# portal.net
KiCad netlist of a schematic drawn in EAGLE
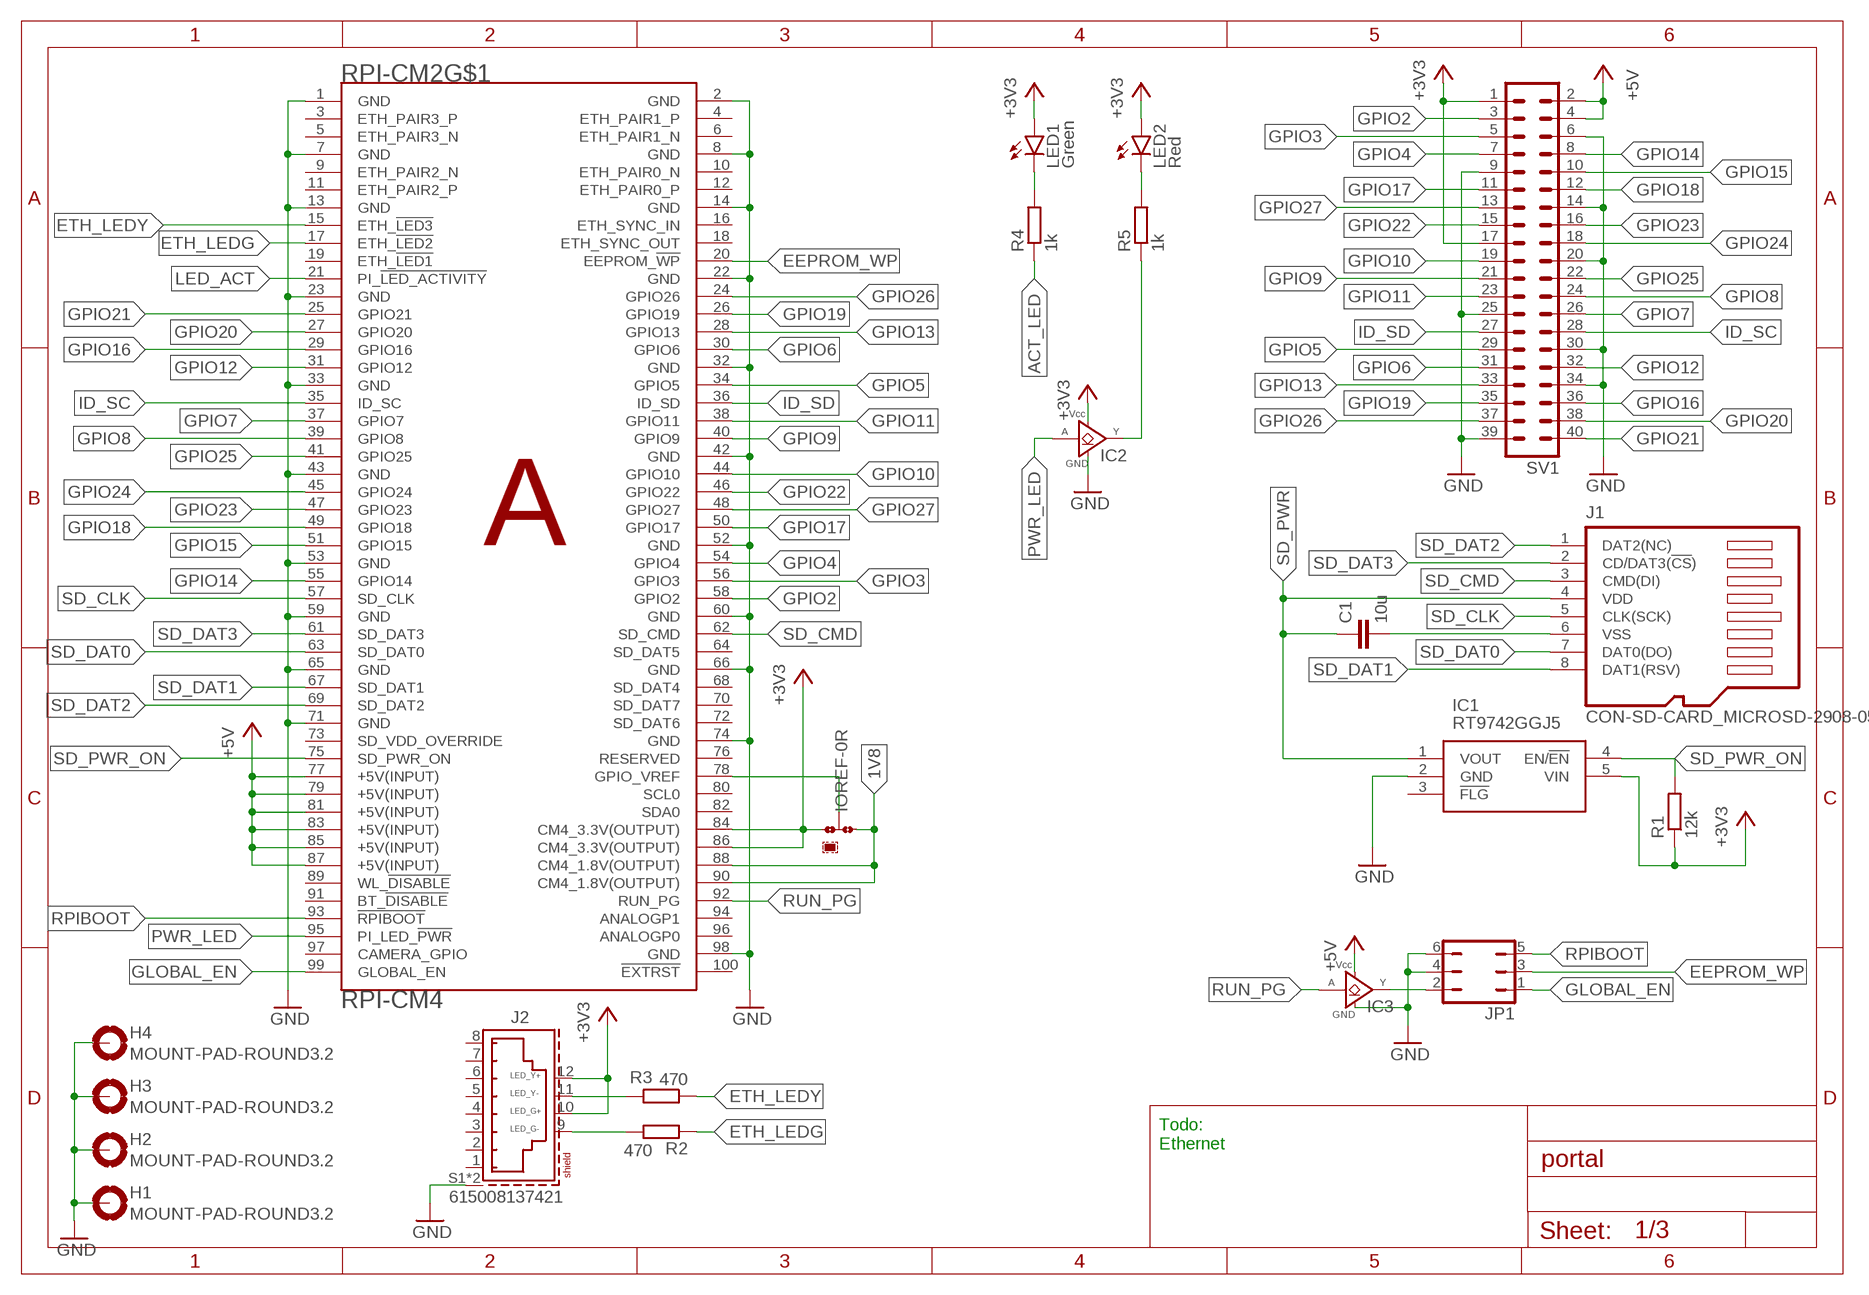
[diagram p0: schematic, sheet 1]
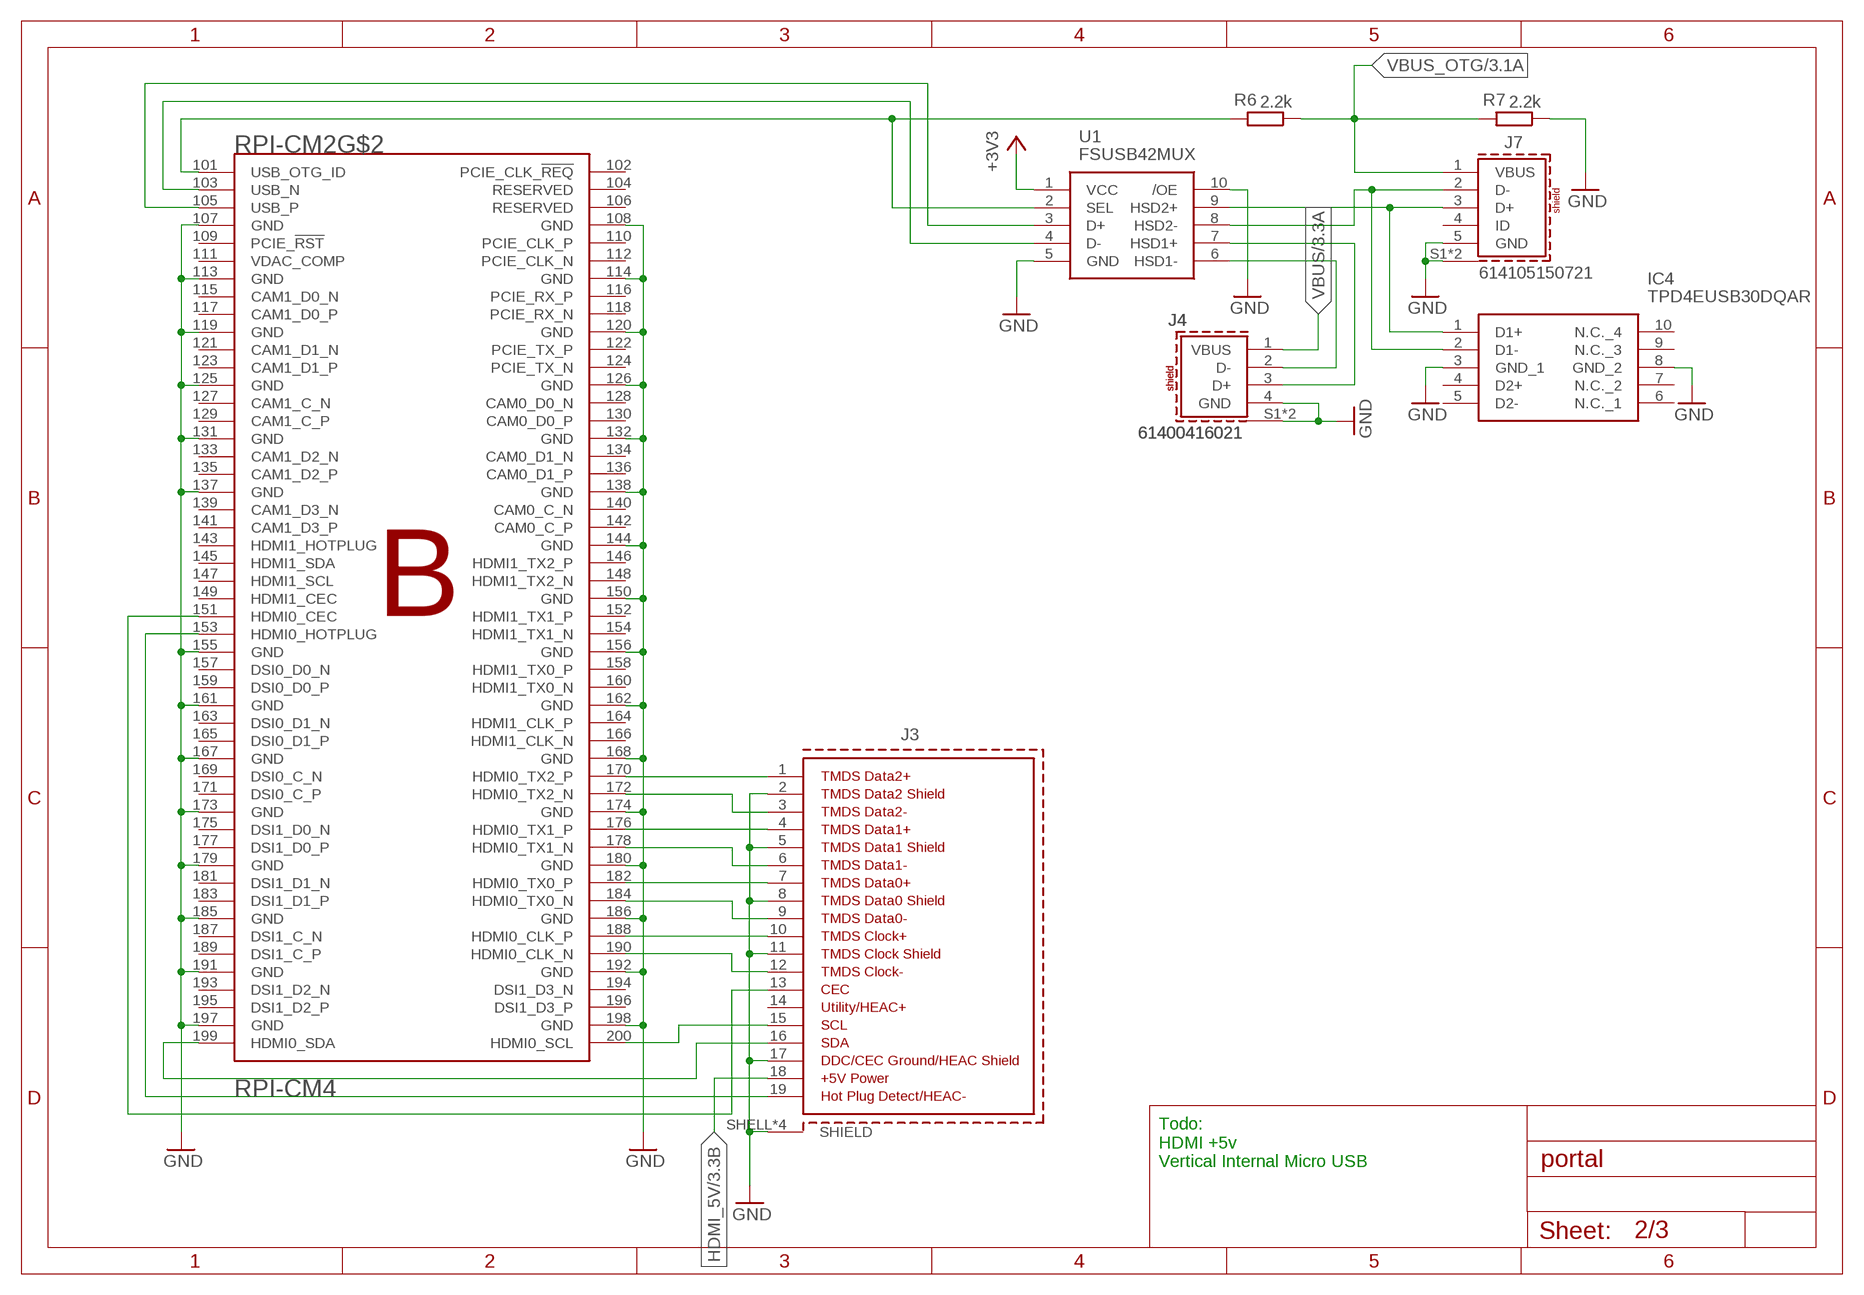
[diagram p1: schematic, sheet 2]
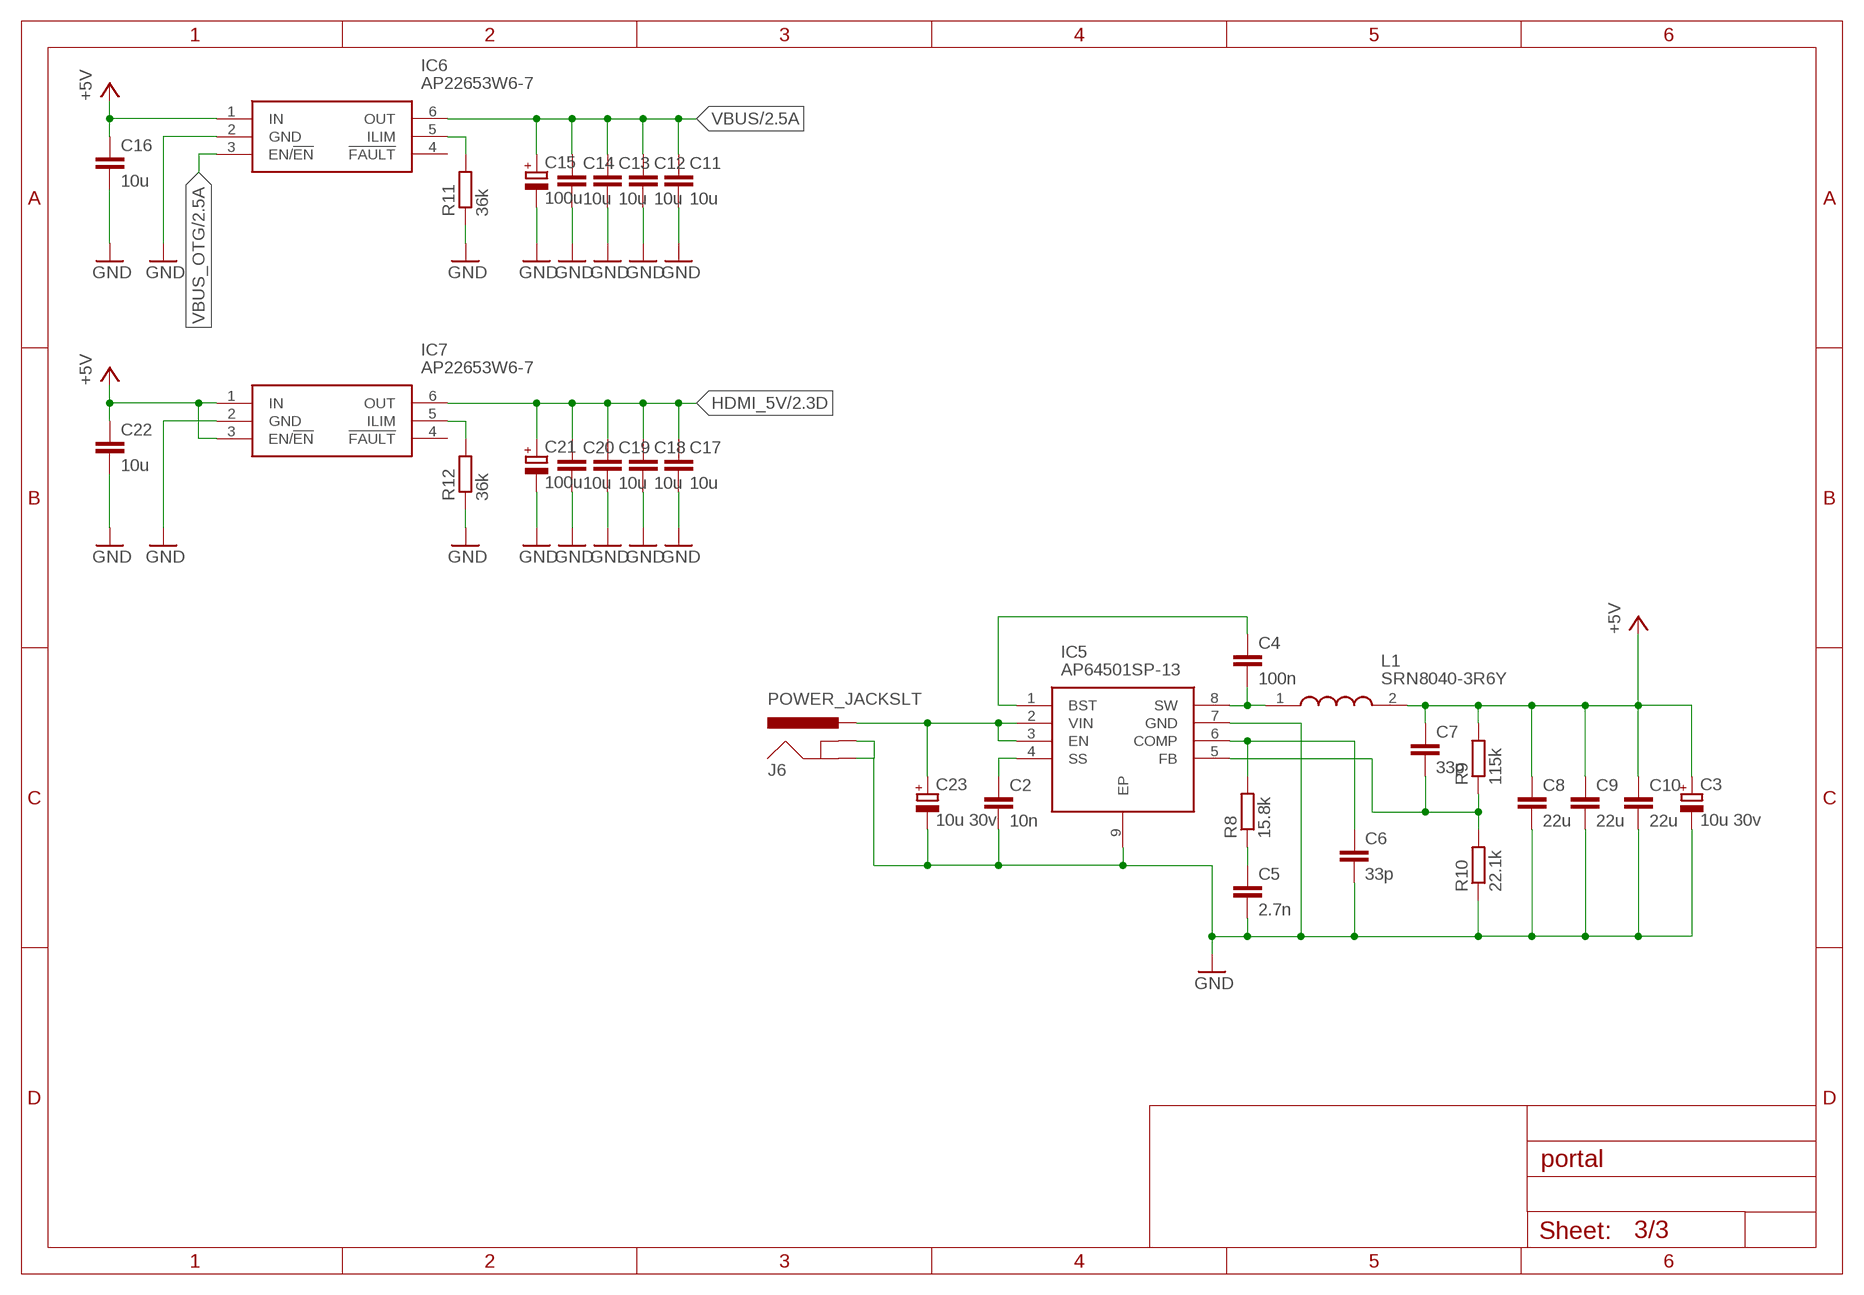
[diagram p2: schematic, sheet 3]

(export (version "E")
  (design (tool "Eeschema 10.0.6"))
  (components
    (comp (ref "C1")
      (value "10u")
      (footprint "eagle-import:C0805")
      (libsource (lib "eagle-import") (part "C-EUC0805"))
    )
    (comp (ref "H1")
      (value "MOUNT-PAD-ROUND3.2")
      (footprint "eagle-import:3,2-PAD")
      (libsource (lib "eagle-import") (part "MOUNT-PAD-ROUND3.2"))
    )
    (comp (ref "H2")
      (value "MOUNT-PAD-ROUND3.2")
      (footprint "eagle-import:3,2-PAD")
      (libsource (lib "eagle-import") (part "MOUNT-PAD-ROUND3.2"))
    )
    (comp (ref "H3")
      (value "MOUNT-PAD-ROUND3.2")
      (footprint "eagle-import:3,2-PAD")
      (libsource (lib "eagle-import") (part "MOUNT-PAD-ROUND3.2"))
    )
    (comp (ref "H4")
      (value "MOUNT-PAD-ROUND3.2")
      (footprint "eagle-import:3,2-PAD")
      (libsource (lib "eagle-import") (part "MOUNT-PAD-ROUND3.2"))
    )
    (comp (ref "IC1")
      (value "RT9742GGJ5")
      (footprint "eagle-import:SOT94P280X100-5N")
      (libsource (lib "eagle-import") (part "RT9742GGJ5"))
    )
    (comp (ref "IC2")
      (value "GHI-IC_SN74LVC1G07DCK")
      (footprint "eagle-import:GHI-IC_SC70(TI-DCK)")
      (libsource (lib "eagle-import") (part "GHI-IC_SN74LVC1G07DCK"))
    )
    (comp (ref "IC3")
      (value "GHI-IC_SN74LVC1G07DCK")
      (footprint "eagle-import:GHI-IC_SC70(TI-DCK)")
      (libsource (lib "eagle-import") (part "GHI-IC_SN74LVC1G07DCK"))
    )
    (comp (ref "IOREF")
      (value "0R-JUMPA")
      (footprint "eagle-import:A0R-JMP")
      (libsource (lib "eagle-import") (part "0R-JUMPA"))
    )
    (comp (ref "J1")
      (value "CON-SD-CARD_MICROSD-2908-05")
      (footprint "eagle-import:CON-SD-CARD_2908-05")
      (libsource (lib "eagle-import") (part "CON-SD-CARD_MICROSD-2908-05"))
    )
    (comp (ref "J2")
      (value "615008137421")
      (footprint "eagle-import:615008137421")
      (libsource (lib "eagle-import") (part "615008137421"))
    )
    (comp (ref "JP1")
      (value "JP3Q")
      (footprint "eagle-import:JP3Q")
      (libsource (lib "eagle-import") (part "JP3Q"))
    )
    (comp (ref "LED1")
      (value "Green")
      (footprint "eagle-import:CHIP-LED0805")
      (libsource (lib "eagle-import") (part "LEDCHIP-LED0805"))
    )
    (comp (ref "LED2")
      (value "Red")
      (footprint "eagle-import:CHIP-LED0805")
      (libsource (lib "eagle-import") (part "LEDCHIP-LED0805"))
    )
    (comp (ref "R1")
      (value "12k")
      (footprint "eagle-import:R0805")
      (libsource (lib "eagle-import") (part "resistor_348_R-EU_R0805"))
    )
    (comp (ref "R2")
      (value "470")
      (footprint "eagle-import:R0805")
      (libsource (lib "eagle-import") (part "R-EU_R0805"))
    )
    (comp (ref "R3")
      (value "470")
      (footprint "eagle-import:R0805")
      (libsource (lib "eagle-import") (part "R-EU_R0805"))
    )
    (comp (ref "R4")
      (value "1k")
      (footprint "eagle-import:R0805")
      (libsource (lib "eagle-import") (part "R-EU_R0805"))
    )
    (comp (ref "R5")
      (value "1k")
      (footprint "eagle-import:R0805")
      (libsource (lib "eagle-import") (part "R-EU_R0805"))
    )
    (comp (ref "RPI-CM2")
      (value "RPI-CM4")
      (footprint "eagle-import:RPI-CM4")
      (libsource (lib "eagle-import") (part "RPI-CM4"))
    )
    (comp (ref "SV1")
      (value "MA20-2")
      (footprint "eagle-import:MA20-2")
      (libsource (lib "eagle-import") (part "MA20-2"))
    )
    (comp (ref "IC4")
      (value "TPD4EUSB30DQAR")
      (footprint "eagle-import:DQA(R-PUSON-N10)")
      (fields (field (name "MOUSER_PART_NUMBER") "595-TPD4EUSB30DQAR"))
      (libsource (lib "eagle-import") (part "TPD4EUSB30DQAR"))
    )
    (comp (ref "J3")
      (value "685119134923")
      (footprint "eagle-import:685119134923")
      (libsource (lib "eagle-import") (part "685119134923"))
    )
    (comp (ref "J4")
      (value "61400416021")
      (footprint "eagle-import:61400416021")
      (libsource (lib "eagle-import") (part "61400416021"))
    )
    (comp (ref "J7")
      (value "614105150721")
      (footprint "eagle-import:614105150721")
      (libsource (lib "eagle-import") (part "614105150721"))
    )
    (comp (ref "R6")
      (value "2.2k")
      (footprint "eagle-import:R0805")
      (libsource (lib "eagle-import") (part "R-EU_R0805"))
    )
    (comp (ref "R7")
      (value "2.2k")
      (footprint "eagle-import:R0805")
      (libsource (lib "eagle-import") (part "R-EU_R0805"))
    )
    (comp (ref "U1")
      (value "FSUSB42MUX")
      (footprint "eagle-import:SOP50P490X110-10N")
      (fields (field (name "MOUSER_PART_NUMBER") "512-FSUSB42MUX"))
      (libsource (lib "eagle-import") (part "FSUSB42MUX"))
    )
    (comp (ref "C2")
      (value "10n")
      (footprint "eagle-import:C0805")
      (libsource (lib "eagle-import") (part "C-EUC0805"))
    )
    (comp (ref "C3")
      (value "10u 30v")
      (footprint "eagle-import:CAPMP7343X310N")
      (libsource (lib "eagle-import") (part "C-POLTANTALUM-2917(7343-METRIC)_"))
    )
    (comp (ref "C4")
      (value "100n")
      (footprint "eagle-import:C0805")
      (libsource (lib "eagle-import") (part "C-EUC0805"))
    )
    (comp (ref "C5")
      (value "2.7n")
      (footprint "eagle-import:C0805")
      (libsource (lib "eagle-import") (part "C-EUC0805"))
    )
    (comp (ref "C6")
      (value "33p")
      (footprint "eagle-import:C0805")
      (libsource (lib "eagle-import") (part "C-EUC0805"))
    )
    (comp (ref "C7")
      (value "33p")
      (footprint "eagle-import:C0805")
      (libsource (lib "eagle-import") (part "C-EUC0805"))
    )
    (comp (ref "C8")
      (value "22u")
      (footprint "eagle-import:C0805")
      (libsource (lib "eagle-import") (part "C-EUC0805"))
    )
    (comp (ref "C9")
      (value "22u")
      (footprint "eagle-import:C0805")
      (libsource (lib "eagle-import") (part "C-EUC0805"))
    )
    (comp (ref "C10")
      (value "22u")
      (footprint "eagle-import:C0805")
      (libsource (lib "eagle-import") (part "C-EUC0805"))
    )
    (comp (ref "C11")
      (value "10u")
      (footprint "eagle-import:C0805")
      (libsource (lib "eagle-import") (part "C-EUC0805"))
    )
    (comp (ref "C12")
      (value "10u")
      (footprint "eagle-import:C0805")
      (libsource (lib "eagle-import") (part "C-EUC0805"))
    )
    (comp (ref "C13")
      (value "10u")
      (footprint "eagle-import:C0805")
      (libsource (lib "eagle-import") (part "C-EUC0805"))
    )
    (comp (ref "C14")
      (value "10u")
      (footprint "eagle-import:C0805")
      (libsource (lib "eagle-import") (part "C-EUC0805"))
    )
    (comp (ref "C15")
      (value "100u")
      (footprint "eagle-import:CAPMP7343X310N")
      (libsource (lib "eagle-import") (part "C-POLTANTALUM-2917(7343-METRIC)_"))
    )
    (comp (ref "C16")
      (value "10u")
      (footprint "eagle-import:C0805")
      (libsource (lib "eagle-import") (part "C-EUC0805"))
    )
    (comp (ref "C17")
      (value "10u")
      (footprint "eagle-import:C0805")
      (libsource (lib "eagle-import") (part "C-EUC0805"))
    )
    (comp (ref "C18")
      (value "10u")
      (footprint "eagle-import:C0805")
      (libsource (lib "eagle-import") (part "C-EUC0805"))
    )
    (comp (ref "C19")
      (value "10u")
      (footprint "eagle-import:C0805")
      (libsource (lib "eagle-import") (part "C-EUC0805"))
    )
    (comp (ref "C20")
      (value "10u")
      (footprint "eagle-import:C0805")
      (libsource (lib "eagle-import") (part "C-EUC0805"))
    )
    (comp (ref "C21")
      (value "100u")
      (footprint "eagle-import:CAPMP7343X310N")
      (libsource (lib "eagle-import") (part "C-POLTANTALUM-2917(7343-METRIC)_"))
    )
    (comp (ref "C22")
      (value "10u")
      (footprint "eagle-import:C0805")
      (libsource (lib "eagle-import") (part "C-EUC0805"))
    )
    (comp (ref "C23")
      (value "10u 30v")
      (footprint "eagle-import:CAPMP7343X310N")
      (libsource (lib "eagle-import") (part "C-POLTANTALUM-2917(7343-METRIC)_"))
    )
    (comp (ref "IC5")
      (value "AP64501SP-13")
      (footprint "eagle-import:SOIC127P600X163-9N")
      (fields (field (name "MOUSER_PART_NUMBER") "621-AP64501SP-13"))
      (libsource (lib "eagle-import") (part "AP64501SP-13"))
    )
    (comp (ref "IC6")
      (value "AP22653W6-7")
      (footprint "eagle-import:SOT95P280X145-6N")
      (fields (field (name "MOUSER_PART_NUMBER") "621-AP22653W6-7"))
      (libsource (lib "eagle-import") (part "AP22653W6-7"))
    )
    (comp (ref "IC7")
      (value "AP22653W6-7")
      (footprint "eagle-import:SOT95P280X145-6N")
      (fields (field (name "MOUSER_PART_NUMBER") "621-AP22653W6-7"))
      (libsource (lib "eagle-import") (part "AP22653W6-7"))
    )
    (comp (ref "J6")
      (value "POWER_JACKSLT")
      (footprint "eagle-import:POWER_JACK_SLOT")
      (libsource (lib "eagle-import") (part "POWER_JACKSLT"))
    )
    (comp (ref "L1")
      (value "SRN8040-3R6Y")
      (footprint "eagle-import:SRN80408R2Y")
      (fields (field (name "MOUSER_PART_NUMBER") "652-SRN8040-3R6Y"))
      (libsource (lib "eagle-import") (part "SRN8040-3R6Y"))
    )
    (comp (ref "R8")
      (value "15.8k")
      (footprint "eagle-import:R0805")
      (libsource (lib "eagle-import") (part "R-EU_R0805"))
    )
    (comp (ref "R9")
      (value "115k")
      (footprint "eagle-import:R0805")
      (libsource (lib "eagle-import") (part "R-EU_R0805"))
    )
    (comp (ref "R10")
      (value "22.1k")
      (footprint "eagle-import:R0805")
      (libsource (lib "eagle-import") (part "R-EU_R0805"))
    )
    (comp (ref "R11")
      (value "36k")
      (footprint "eagle-import:R0805")
      (libsource (lib "eagle-import") (part "R-EU_R0805"))
    )
    (comp (ref "R12")
      (value "36k")
      (footprint "eagle-import:R0805")
      (libsource (lib "eagle-import") (part "R-EU_R0805"))
    )
  )
  (nets
    (net (code "1") (name "+3V3") (class "Default")
      (node (ref "IC1") (pin "5") (pinfunction "VIN_5") (pintype "bidirectional"))
      (node (ref "IC2") (pin "5") (pinfunction "VCC_5") (pintype "bidirectional"))
      (node (ref "IOREF") (pin "1") (pinfunction "1_1") (pintype "passive"))
      (node (ref "J2") (pin "10") (pinfunction "G+_10") (pintype "passive"))
      (node (ref "J2") (pin "12") (pinfunction "Y+_12") (pintype "passive"))
      (node (ref "LED1") (pin "A") (pinfunction "A_A") (pintype "passive"))
      (node (ref "LED2") (pin "A") (pinfunction "A_A") (pintype "passive"))
      (node (ref "R1") (pin "1") (pinfunction "1_1") (pintype "passive"))
      (node (ref "RPI-CM2") (pin "84") (pinfunction "CM4_3.3V(OUTPUT)_84") (pintype "passive"))
      (node (ref "RPI-CM2") (pin "86") (pinfunction "CM4_3.3V(OUTPUT)_86") (pintype "passive"))
      (node (ref "SV1") (pin "1") (pinfunction "1_1") (pintype "passive"))
      (node (ref "SV1") (pin "17") (pinfunction "17_17") (pintype "passive"))
      (node (ref "U1") (pin "1") (pinfunction "VCC_1") (pintype "bidirectional"))
    )
    (net (code "2") (name "+5V") (class "Default")
      (node (ref "C10") (pin "1") (pinfunction "1_1") (pintype "passive"))
      (node (ref "C16") (pin "1") (pinfunction "1_1") (pintype "passive"))
      (node (ref "C22") (pin "1") (pinfunction "1_1") (pintype "passive"))
      (node (ref "C3") (pin "1") (pinfunction "+_1") (pintype "passive"))
      (node (ref "C7") (pin "1") (pinfunction "1_1") (pintype "passive"))
      (node (ref "C8") (pin "1") (pinfunction "1_1") (pintype "passive"))
      (node (ref "C9") (pin "1") (pinfunction "1_1") (pintype "passive"))
      (node (ref "IC3") (pin "5") (pinfunction "VCC_5") (pintype "bidirectional"))
      (node (ref "IC6") (pin "1") (pinfunction "IN_1") (pintype "bidirectional"))
      (node (ref "IC7") (pin "1") (pinfunction "IN_1") (pintype "bidirectional"))
      (node (ref "IC7") (pin "3") (pinfunction "EN/~{EN}_3") (pintype "bidirectional"))
      (node (ref "L1") (pin "2") (pinfunction "2_2") (pintype "bidirectional"))
      (node (ref "R9") (pin "2") (pinfunction "2_2") (pintype "passive"))
      (node (ref "RPI-CM2") (pin "77") (pinfunction "+5V(INPUT)_77") (pintype "passive"))
      (node (ref "RPI-CM2") (pin "79") (pinfunction "+5V(INPUT)_79") (pintype "passive"))
      (node (ref "RPI-CM2") (pin "81") (pinfunction "+5V(INPUT)_81") (pintype "passive"))
      (node (ref "RPI-CM2") (pin "83") (pinfunction "+5V(INPUT)_83") (pintype "passive"))
      (node (ref "RPI-CM2") (pin "85") (pinfunction "+5V(INPUT)_85") (pintype "passive"))
      (node (ref "RPI-CM2") (pin "87") (pinfunction "+5V(INPUT)_87") (pintype "passive"))
      (node (ref "SV1") (pin "2") (pinfunction "2_2") (pintype "passive"))
      (node (ref "SV1") (pin "4") (pinfunction "4_4") (pintype "passive"))
    )
    (net (code "3") (name "1V8") (class "Default")
      (node (ref "IOREF") (pin "3") (pinfunction "3_3") (pintype "passive"))
      (node (ref "RPI-CM2") (pin "88") (pinfunction "CM4_1.8V(OUTPUT)_88") (pintype "passive"))
      (node (ref "RPI-CM2") (pin "90") (pinfunction "CM4_1.8V(OUTPUT)_90") (pintype "passive"))
    )
    (net (code "4") (name "ACT_LED") (class "Default")
      (node (ref "R4") (pin "1") (pinfunction "1_1") (pintype "passive"))
    )
    (net (code "5") (name "EEPROM_WP") (class "Default")
      (node (ref "JP1") (pin "3") (pinfunction "3_3") (pintype "passive"))
      (node (ref "RPI-CM2") (pin "20") (pinfunction "EEPROM_~{WP}_20") (pintype "passive"))
    )
    (net (code "6") (name "ETH_LEDG") (class "Default")
      (node (ref "R2") (pin "1") (pinfunction "1_1") (pintype "passive"))
      (node (ref "RPI-CM2") (pin "17") (pinfunction "ETH_~{LED2}_17") (pintype "passive"))
    )
    (net (code "7") (name "ETH_LEDY") (class "Default")
      (node (ref "R3") (pin "1") (pinfunction "1_1") (pintype "passive"))
      (node (ref "RPI-CM2") (pin "15") (pinfunction "ETH_~{LED3}_15") (pintype "passive"))
    )
    (net (code "8") (name "GLOBAL_EN") (class "Default")
      (node (ref "JP1") (pin "1") (pinfunction "1_1") (pintype "passive"))
      (node (ref "RPI-CM2") (pin "99") (pinfunction "GLOBAL_EN_99") (pintype "passive"))
    )
    (net (code "9") (name "GND") (class "Default")
      (node (ref "C10") (pin "2") (pinfunction "2_2") (pintype "passive"))
      (node (ref "C11") (pin "2") (pinfunction "2_2") (pintype "passive"))
      (node (ref "C12") (pin "2") (pinfunction "2_2") (pintype "passive"))
      (node (ref "C13") (pin "2") (pinfunction "2_2") (pintype "passive"))
      (node (ref "C14") (pin "2") (pinfunction "2_2") (pintype "passive"))
      (node (ref "C15") (pin "2") (pinfunction "-_2") (pintype "passive"))
      (node (ref "C16") (pin "2") (pinfunction "2_2") (pintype "passive"))
      (node (ref "C17") (pin "2") (pinfunction "2_2") (pintype "passive"))
      (node (ref "C18") (pin "2") (pinfunction "2_2") (pintype "passive"))
      (node (ref "C19") (pin "2") (pinfunction "2_2") (pintype "passive"))
      (node (ref "C2") (pin "2") (pinfunction "2_2") (pintype "passive"))
      (node (ref "C20") (pin "2") (pinfunction "2_2") (pintype "passive"))
      (node (ref "C21") (pin "2") (pinfunction "-_2") (pintype "passive"))
      (node (ref "C22") (pin "2") (pinfunction "2_2") (pintype "passive"))
      (node (ref "C23") (pin "2") (pinfunction "-_2") (pintype "passive"))
      (node (ref "C3") (pin "2") (pinfunction "-_2") (pintype "passive"))
      (node (ref "C5") (pin "2") (pinfunction "2_2") (pintype "passive"))
      (node (ref "C6") (pin "2") (pinfunction "2_2") (pintype "passive"))
      (node (ref "C8") (pin "2") (pinfunction "2_2") (pintype "passive"))
      (node (ref "C9") (pin "2") (pinfunction "2_2") (pintype "passive"))
      (node (ref "H1") (pin "B3,2") (pinfunction "MOUNT_B3,2") (pintype "passive"))
      (node (ref "H2") (pin "B3,2") (pinfunction "MOUNT_B3,2") (pintype "passive"))
      (node (ref "H3") (pin "B3,2") (pinfunction "MOUNT_B3,2") (pintype "passive"))
      (node (ref "H4") (pin "B3,2") (pinfunction "MOUNT_B3,2") (pintype "passive"))
      (node (ref "IC1") (pin "2") (pinfunction "GND_2") (pintype "bidirectional"))
      (node (ref "IC2") (pin "3") (pinfunction "GND_3") (pintype "bidirectional"))
      (node (ref "IC3") (pin "3") (pinfunction "GND_3") (pintype "bidirectional"))
      (node (ref "IC4") (pin "3") (pinfunction "GND_1_3") (pintype "bidirectional"))
      (node (ref "IC4") (pin "8") (pinfunction "GND_2_8") (pintype "bidirectional"))
      (node (ref "IC5") (pin "7") (pinfunction "GND_7") (pintype "bidirectional"))
      (node (ref "IC5") (pin "9") (pinfunction "EP_9") (pintype "bidirectional"))
      (node (ref "IC6") (pin "2") (pinfunction "GND_2") (pintype "bidirectional"))
      (node (ref "IC7") (pin "2") (pinfunction "GND_2") (pintype "bidirectional"))
      (node (ref "J2") (pin "S1") (pinfunction "SHIELD_S1") (pintype "passive"))
      (node (ref "J2") (pin "S2") (pinfunction "SHIELD_S2") (pintype "passive"))
      (node (ref "J3") (pin "11") (pinfunction "TMDSCLOCKSHIELD_11") (pintype "passive"))
      (node (ref "J3") (pin "17") (pinfunction "DDC/CEC/HECGROUND_17") (pintype "passive"))
      (node (ref "J3") (pin "2") (pinfunction "TMDSDATA2SHIELD_2") (pintype "passive"))
      (node (ref "J3") (pin "5") (pinfunction "TMDSDATA1SHIELD_5") (pintype "passive"))
      (node (ref "J3") (pin "8") (pinfunction "TMDSDATA0SHIELD_8") (pintype "passive"))
      (node (ref "J3") (pin "SHELL") (pinfunction "SHIELD_SHELL") (pintype "passive"))
      (node (ref "J3") (pin "SHELL1") (pinfunction "SHIELD_SHELL1") (pintype "passive"))
      (node (ref "J3") (pin "SHELL2") (pinfunction "SHIELD_SHELL2") (pintype "passive"))
      (node (ref "J3") (pin "SHELL3") (pinfunction "SHIELD_SHELL3") (pintype "passive"))
      (node (ref "J4") (pin "4") (pinfunction "GND_4") (pintype "bidirectional"))
      (node (ref "J4") (pin "S1") (pinfunction "SHIELD_S1") (pintype "bidirectional"))
      (node (ref "J4") (pin "S2") (pinfunction "SHIELD_S2") (pintype "bidirectional"))
      (node (ref "J6") (pin "GND@1") (pinfunction "GNDBREAK_GND@1") (pintype "bidirectional"))
      (node (ref "J6") (pin "GND@2") (pinfunction "GND_GND@2") (pintype "bidirectional"))
      (node (ref "J7") (pin "5") (pinfunction "GND_5") (pintype "passive"))
      (node (ref "J7") (pin "S1") (pinfunction "SHIELD_S1") (pintype "passive"))
      (node (ref "J7") (pin "S2") (pinfunction "SHIELD_S2") (pintype "passive"))
      (node (ref "JP1") (pin "4") (pinfunction "4_4") (pintype "passive"))
      (node (ref "JP1") (pin "6") (pinfunction "6_6") (pintype "passive"))
      (node (ref "R10") (pin "1") (pinfunction "1_1") (pintype "passive"))
      (node (ref "R11") (pin "1") (pinfunction "1_1") (pintype "passive"))
      (node (ref "R12") (pin "1") (pinfunction "1_1") (pintype "passive"))
      (node (ref "R7") (pin "1") (pinfunction "1_1") (pintype "passive"))
      (node (ref "RPI-CM2") (pin "1") (pinfunction "GND_1") (pintype "passive"))
      (node (ref "RPI-CM2") (pin "107") (pinfunction "GND_107") (pintype "passive"))
      (node (ref "RPI-CM2") (pin "108") (pinfunction "GND_108") (pintype "passive"))
      (node (ref "RPI-CM2") (pin "113") (pinfunction "GND_113") (pintype "passive"))
      (node (ref "RPI-CM2") (pin "114") (pinfunction "GND_114") (pintype "passive"))
      (node (ref "RPI-CM2") (pin "119") (pinfunction "GND_119") (pintype "passive"))
      (node (ref "RPI-CM2") (pin "120") (pinfunction "GND_120") (pintype "passive"))
      (node (ref "RPI-CM2") (pin "125") (pinfunction "GND_125") (pintype "passive"))
      (node (ref "RPI-CM2") (pin "126") (pinfunction "GND_126") (pintype "passive"))
      (node (ref "RPI-CM2") (pin "13") (pinfunction "GND_13") (pintype "passive"))
      (node (ref "RPI-CM2") (pin "131") (pinfunction "GND_131") (pintype "passive"))
      (node (ref "RPI-CM2") (pin "132") (pinfunction "GND_132") (pintype "passive"))
      (node (ref "RPI-CM2") (pin "137") (pinfunction "GND_137") (pintype "passive"))
      (node (ref "RPI-CM2") (pin "138") (pinfunction "GND_138") (pintype "passive"))
      (node (ref "RPI-CM2") (pin "14") (pinfunction "GND_14") (pintype "passive"))
      (node (ref "RPI-CM2") (pin "144") (pinfunction "GND_144") (pintype "passive"))
      (node (ref "RPI-CM2") (pin "150") (pinfunction "GND_150") (pintype "passive"))
      (node (ref "RPI-CM2") (pin "155") (pinfunction "GND_155") (pintype "passive"))
      (node (ref "RPI-CM2") (pin "156") (pinfunction "GND_156") (pintype "passive"))
      (node (ref "RPI-CM2") (pin "161") (pinfunction "GND_161") (pintype "passive"))
      (node (ref "RPI-CM2") (pin "162") (pinfunction "GND_162") (pintype "passive"))
      (node (ref "RPI-CM2") (pin "167") (pinfunction "GND_167") (pintype "passive"))
      (node (ref "RPI-CM2") (pin "168") (pinfunction "GND_168") (pintype "passive"))
      (node (ref "RPI-CM2") (pin "173") (pinfunction "GND_173") (pintype "passive"))
      (node (ref "RPI-CM2") (pin "174") (pinfunction "GND_174") (pintype "passive"))
      (node (ref "RPI-CM2") (pin "179") (pinfunction "GND_179") (pintype "passive"))
      (node (ref "RPI-CM2") (pin "180") (pinfunction "GND_180") (pintype "passive"))
      (node (ref "RPI-CM2") (pin "185") (pinfunction "GND_185") (pintype "passive"))
      (node (ref "RPI-CM2") (pin "186") (pinfunction "GND_186") (pintype "passive"))
      (node (ref "RPI-CM2") (pin "191") (pinfunction "GND_191") (pintype "passive"))
      (node (ref "RPI-CM2") (pin "192") (pinfunction "GND_192") (pintype "passive"))
      (node (ref "RPI-CM2") (pin "197") (pinfunction "GND_197") (pintype "passive"))
      (node (ref "RPI-CM2") (pin "198") (pinfunction "GND_198") (pintype "passive"))
      (node (ref "RPI-CM2") (pin "2") (pinfunction "GND_2") (pintype "passive"))
      (node (ref "RPI-CM2") (pin "22") (pinfunction "GND_22") (pintype "passive"))
      (node (ref "RPI-CM2") (pin "23") (pinfunction "GND_23") (pintype "passive"))
      (node (ref "RPI-CM2") (pin "32") (pinfunction "GND_32") (pintype "passive"))
      (node (ref "RPI-CM2") (pin "33") (pinfunction "GND_33") (pintype "passive"))
      (node (ref "RPI-CM2") (pin "42") (pinfunction "GND_42") (pintype "passive"))
      (node (ref "RPI-CM2") (pin "43") (pinfunction "GND_43") (pintype "passive"))
      (node (ref "RPI-CM2") (pin "52") (pinfunction "GND_52") (pintype "passive"))
      (node (ref "RPI-CM2") (pin "53") (pinfunction "GND_53") (pintype "passive"))
      (node (ref "RPI-CM2") (pin "59") (pinfunction "GND_59") (pintype "passive"))
      (node (ref "RPI-CM2") (pin "60") (pinfunction "GND_60") (pintype "passive"))
      (node (ref "RPI-CM2") (pin "65") (pinfunction "GND_65") (pintype "passive"))
      (node (ref "RPI-CM2") (pin "66") (pinfunction "GND_66") (pintype "passive"))
      (node (ref "RPI-CM2") (pin "7") (pinfunction "GND_7") (pintype "passive"))
      (node (ref "RPI-CM2") (pin "71") (pinfunction "GND_71") (pintype "passive"))
      (node (ref "RPI-CM2") (pin "74") (pinfunction "GND_74") (pintype "passive"))
      (node (ref "RPI-CM2") (pin "8") (pinfunction "GND_8") (pintype "passive"))
      (node (ref "RPI-CM2") (pin "98") (pinfunction "GND_98") (pintype "passive"))
      (node (ref "SV1") (pin "14") (pinfunction "14_14") (pintype "passive"))
      (node (ref "SV1") (pin "20") (pinfunction "20_20") (pintype "passive"))
      (node (ref "SV1") (pin "25") (pinfunction "25_25") (pintype "passive"))
      (node (ref "SV1") (pin "30") (pinfunction "30_30") (pintype "passive"))
      (node (ref "SV1") (pin "34") (pinfunction "34_34") (pintype "passive"))
      (node (ref "SV1") (pin "39") (pinfunction "39_39") (pintype "passive"))
      (node (ref "SV1") (pin "6") (pinfunction "6_6") (pintype "passive"))
      (node (ref "SV1") (pin "9") (pinfunction "9_9") (pintype "passive"))
      (node (ref "U1") (pin "10") (pinfunction "/OE_10") (pintype "bidirectional"))
      (node (ref "U1") (pin "5") (pinfunction "GND_5") (pintype "bidirectional"))
    )
    (net (code "10") (name "GPIO2") (class "Default")
      (node (ref "RPI-CM2") (pin "58") (pinfunction "GPIO2_58") (pintype "passive"))
      (node (ref "SV1") (pin "3") (pinfunction "3_3") (pintype "passive"))
    )
    (net (code "11") (name "GPIO3") (class "Default")
      (node (ref "RPI-CM2") (pin "56") (pinfunction "GPIO3_56") (pintype "passive"))
      (node (ref "SV1") (pin "5") (pinfunction "5_5") (pintype "passive"))
    )
    (net (code "12") (name "GPIO4") (class "Default")
      (node (ref "RPI-CM2") (pin "54") (pinfunction "GPIO4_54") (pintype "passive"))
      (node (ref "SV1") (pin "7") (pinfunction "7_7") (pintype "passive"))
    )
    (net (code "13") (name "GPIO5") (class "Default")
      (node (ref "RPI-CM2") (pin "34") (pinfunction "GPIO5_34") (pintype "passive"))
      (node (ref "SV1") (pin "29") (pinfunction "29_29") (pintype "passive"))
    )
    (net (code "14") (name "GPIO6") (class "Default")
      (node (ref "RPI-CM2") (pin "30") (pinfunction "GPIO6_30") (pintype "passive"))
      (node (ref "SV1") (pin "31") (pinfunction "31_31") (pintype "passive"))
    )
    (net (code "15") (name "GPIO7") (class "Default")
      (node (ref "RPI-CM2") (pin "37") (pinfunction "GPIO7_37") (pintype "passive"))
      (node (ref "SV1") (pin "26") (pinfunction "26_26") (pintype "passive"))
    )
    (net (code "16") (name "GPIO8") (class "Default")
      (node (ref "RPI-CM2") (pin "39") (pinfunction "GPIO8_39") (pintype "passive"))
      (node (ref "SV1") (pin "24") (pinfunction "24_24") (pintype "passive"))
    )
    (net (code "17") (name "GPIO9") (class "Default")
      (node (ref "RPI-CM2") (pin "40") (pinfunction "GPIO9_40") (pintype "passive"))
      (node (ref "SV1") (pin "21") (pinfunction "21_21") (pintype "passive"))
    )
    (net (code "18") (name "GPIO10") (class "Default")
      (node (ref "RPI-CM2") (pin "44") (pinfunction "GPIO10_44") (pintype "passive"))
      (node (ref "SV1") (pin "19") (pinfunction "19_19") (pintype "passive"))
    )
    (net (code "19") (name "GPIO11") (class "Default")
      (node (ref "RPI-CM2") (pin "38") (pinfunction "GPIO11_38") (pintype "passive"))
      (node (ref "SV1") (pin "23") (pinfunction "23_23") (pintype "passive"))
    )
    (net (code "20") (name "GPIO12") (class "Default")
      (node (ref "RPI-CM2") (pin "31") (pinfunction "GPIO12_31") (pintype "passive"))
      (node (ref "SV1") (pin "32") (pinfunction "32_32") (pintype "passive"))
    )
    (net (code "21") (name "GPIO13") (class "Default")
      (node (ref "RPI-CM2") (pin "28") (pinfunction "GPIO13_28") (pintype "passive"))
      (node (ref "SV1") (pin "33") (pinfunction "33_33") (pintype "passive"))
    )
    (net (code "22") (name "GPIO14") (class "Default")
      (node (ref "RPI-CM2") (pin "55") (pinfunction "GPIO14_55") (pintype "passive"))
      (node (ref "SV1") (pin "8") (pinfunction "8_8") (pintype "passive"))
    )
    (net (code "23") (name "GPIO15") (class "Default")
      (node (ref "RPI-CM2") (pin "51") (pinfunction "GPIO15_51") (pintype "passive"))
      (node (ref "SV1") (pin "10") (pinfunction "10_10") (pintype "passive"))
    )
    (net (code "24") (name "GPIO16") (class "Default")
      (node (ref "RPI-CM2") (pin "29") (pinfunction "GPIO16_29") (pintype "passive"))
      (node (ref "SV1") (pin "36") (pinfunction "36_36") (pintype "passive"))
    )
    (net (code "25") (name "GPIO17") (class "Default")
      (node (ref "RPI-CM2") (pin "50") (pinfunction "GPIO17_50") (pintype "passive"))
      (node (ref "SV1") (pin "11") (pinfunction "11_11") (pintype "passive"))
    )
    (net (code "26") (name "GPIO18") (class "Default")
      (node (ref "RPI-CM2") (pin "49") (pinfunction "GPIO18_49") (pintype "passive"))
      (node (ref "SV1") (pin "12") (pinfunction "12_12") (pintype "passive"))
    )
    (net (code "27") (name "GPIO19") (class "Default")
      (node (ref "RPI-CM2") (pin "26") (pinfunction "GPIO19_26") (pintype "passive"))
      (node (ref "SV1") (pin "35") (pinfunction "35_35") (pintype "passive"))
    )
    (net (code "28") (name "GPIO20") (class "Default")
      (node (ref "RPI-CM2") (pin "27") (pinfunction "GPIO20_27") (pintype "passive"))
      (node (ref "SV1") (pin "38") (pinfunction "38_38") (pintype "passive"))
    )
    (net (code "29") (name "GPIO21") (class "Default")
      (node (ref "RPI-CM2") (pin "25") (pinfunction "GPIO21_25") (pintype "passive"))
      (node (ref "SV1") (pin "40") (pinfunction "40_40") (pintype "passive"))
    )
    (net (code "30") (name "GPIO22") (class "Default")
      (node (ref "RPI-CM2") (pin "46") (pinfunction "GPIO22_46") (pintype "passive"))
      (node (ref "SV1") (pin "15") (pinfunction "15_15") (pintype "passive"))
    )
    (net (code "31") (name "GPIO23") (class "Default")
      (node (ref "RPI-CM2") (pin "47") (pinfunction "GPIO23_47") (pintype "passive"))
      (node (ref "SV1") (pin "16") (pinfunction "16_16") (pintype "passive"))
    )
    (net (code "32") (name "GPIO24") (class "Default")
      (node (ref "RPI-CM2") (pin "45") (pinfunction "GPIO24_45") (pintype "passive"))
      (node (ref "SV1") (pin "18") (pinfunction "18_18") (pintype "passive"))
    )
    (net (code "33") (name "GPIO25") (class "Default")
      (node (ref "RPI-CM2") (pin "41") (pinfunction "GPIO25_41") (pintype "passive"))
      (node (ref "SV1") (pin "22") (pinfunction "22_22") (pintype "passive"))
    )
    (net (code "34") (name "GPIO26") (class "Default")
      (node (ref "RPI-CM2") (pin "24") (pinfunction "GPIO26_24") (pintype "passive"))
      (node (ref "SV1") (pin "37") (pinfunction "37_37") (pintype "passive"))
    )
    (net (code "35") (name "GPIO27") (class "Default")
      (node (ref "RPI-CM2") (pin "48") (pinfunction "GPIO27_48") (pintype "passive"))
      (node (ref "SV1") (pin "13") (pinfunction "13_13") (pintype "passive"))
    )
    (net (code "36") (name "HDMI_5V") (class "Default")
      (node (ref "C17") (pin "1") (pinfunction "1_1") (pintype "passive"))
      (node (ref "C18") (pin "1") (pinfunction "1_1") (pintype "passive"))
      (node (ref "C19") (pin "1") (pinfunction "1_1") (pintype "passive"))
      (node (ref "C20") (pin "1") (pinfunction "1_1") (pintype "passive"))
      (node (ref "C21") (pin "1") (pinfunction "+_1") (pintype "passive"))
      (node (ref "IC7") (pin "6") (pinfunction "OUT_6") (pintype "bidirectional"))
      (node (ref "J3") (pin "18") (pinfunction "+5VPOWER_18") (pintype "power_in"))
    )
    (net (code "37") (name "ID_SC") (class "Default")
      (node (ref "RPI-CM2") (pin "35") (pinfunction "ID_SC_35") (pintype "passive"))
      (node (ref "SV1") (pin "28") (pinfunction "28_28") (pintype "passive"))
    )
    (net (code "38") (name "ID_SD") (class "Default")
      (node (ref "RPI-CM2") (pin "36") (pinfunction "ID_SD_36") (pintype "passive"))
      (node (ref "SV1") (pin "27") (pinfunction "27_27") (pintype "passive"))
    )
    (net (code "39") (name "LED_ACT") (class "Default")
      (node (ref "RPI-CM2") (pin "21") (pinfunction "PI_~{LED_ACTIVITY}_21") (pintype "passive"))
    )
    (net (code "40") (name "Net-(C5-Pad1)") (class "Default")
      (node (ref "C5") (pin "1") (pinfunction "1_1") (pintype "passive"))
      (node (ref "R8") (pin "1") (pinfunction "1_1") (pintype "passive"))
    )
    (net (code "41") (name "Net-(C23-+)") (class "Default")
      (node (ref "C23") (pin "1") (pinfunction "+_1") (pintype "passive"))
      (node (ref "IC5") (pin "2") (pinfunction "VIN_2") (pintype "bidirectional"))
      (node (ref "IC5") (pin "3") (pinfunction "EN_3") (pintype "bidirectional"))
      (node (ref "J6") (pin "PWR") (pinfunction "PWR_PWR") (pintype "bidirectional"))
    )
    (net (code "42") (name "Net-(IC2-Y)") (class "Default")
      (node (ref "IC2") (pin "4") (pinfunction "Y_4") (pintype "bidirectional"))
      (node (ref "R5") (pin "1") (pinfunction "1_1") (pintype "passive"))
    )
    (net (code "43") (name "Net-(IC3-Y)") (class "Default")
      (node (ref "IC3") (pin "4") (pinfunction "Y_4") (pintype "bidirectional"))
      (node (ref "JP1") (pin "2") (pinfunction "2_2") (pintype "passive"))
    )
    (net (code "44") (name "Net-(IC4-D1+)") (class "Default")
      (node (ref "IC4") (pin "1") (pinfunction "D1+_1") (pintype "bidirectional"))
      (node (ref "J7") (pin "3") (pinfunction "D+_3") (pintype "passive"))
      (node (ref "U1") (pin "9") (pinfunction "HSD2+_9") (pintype "bidirectional"))
    )
    (net (code "45") (name "Net-(IC4-D1-)") (class "Default")
      (node (ref "IC4") (pin "2") (pinfunction "D1-_2") (pintype "bidirectional"))
      (node (ref "J7") (pin "2") (pinfunction "D-_2") (pintype "passive"))
      (node (ref "U1") (pin "8") (pinfunction "HSD2-_8") (pintype "bidirectional"))
    )
    (net (code "46") (name "Net-(IC5-BST)") (class "Default")
      (node (ref "C4") (pin "1") (pinfunction "1_1") (pintype "passive"))
      (node (ref "IC5") (pin "1") (pinfunction "BST_1") (pintype "bidirectional"))
    )
    (net (code "47") (name "Net-(IC5-COMP)") (class "Default")
      (node (ref "C6") (pin "1") (pinfunction "1_1") (pintype "passive"))
      (node (ref "IC5") (pin "6") (pinfunction "COMP_6") (pintype "bidirectional"))
      (node (ref "R8") (pin "2") (pinfunction "2_2") (pintype "passive"))
    )
    (net (code "48") (name "Net-(IC5-FB)") (class "Default")
      (node (ref "C7") (pin "2") (pinfunction "2_2") (pintype "passive"))
      (node (ref "IC5") (pin "5") (pinfunction "FB_5") (pintype "bidirectional"))
      (node (ref "R10") (pin "2") (pinfunction "2_2") (pintype "passive"))
      (node (ref "R9") (pin "1") (pinfunction "1_1") (pintype "passive"))
    )
    (net (code "49") (name "Net-(IC5-SS)") (class "Default")
      (node (ref "C2") (pin "1") (pinfunction "1_1") (pintype "passive"))
      (node (ref "IC5") (pin "4") (pinfunction "SS_4") (pintype "bidirectional"))
    )
    (net (code "50") (name "Net-(IC5-SW)") (class "Default")
      (node (ref "C4") (pin "2") (pinfunction "2_2") (pintype "passive"))
      (node (ref "IC5") (pin "8") (pinfunction "SW_8") (pintype "bidirectional"))
      (node (ref "L1") (pin "1") (pinfunction "1_1") (pintype "bidirectional"))
    )
    (net (code "51") (name "Net-(IC6-ILIM)") (class "Default")
      (node (ref "IC6") (pin "5") (pinfunction "ILIM_5") (pintype "bidirectional"))
      (node (ref "R11") (pin "2") (pinfunction "2_2") (pintype "passive"))
    )
    (net (code "52") (name "Net-(IC7-ILIM)") (class "Default")
      (node (ref "IC7") (pin "5") (pinfunction "ILIM_5") (pintype "bidirectional"))
      (node (ref "R12") (pin "2") (pinfunction "2_2") (pintype "passive"))
    )
    (net (code "53") (name "Net-(J1B-VSS)") (class "Default")
      (node (ref "C1") (pin "2") (pinfunction "2_2") (pintype "passive"))
      (node (ref "J1") (pin "6") (pinfunction "VSS_6") (pintype "bidirectional"))
    )
    (net (code "54") (name "Net-(J2-G-)") (class "Default")
      (node (ref "J2") (pin "9") (pinfunction "G-_9") (pintype "passive"))
      (node (ref "R2") (pin "2") (pinfunction "2_2") (pintype "passive"))
    )
    (net (code "55") (name "Net-(J2-Y-)") (class "Default")
      (node (ref "J2") (pin "11") (pinfunction "Y-_11") (pintype "passive"))
      (node (ref "R3") (pin "2") (pinfunction "2_2") (pintype "passive"))
    )
    (net (code "56") (name "Net-(J3-CEC)") (class "Default")
      (node (ref "J3") (pin "13") (pinfunction "CEC_13") (pintype "passive"))
      (node (ref "RPI-CM2") (pin "151") (pinfunction "HDMI0_CEC_151") (pintype "passive"))
    )
    (net (code "57") (name "Net-(J3-HOTPLUGDETECT{slash}HEAC-)") (class "Default")
      (node (ref "J3") (pin "19") (pinfunction "HOTPLUGDETECT/HEAC-_19") (pintype "passive"))
      (node (ref "RPI-CM2") (pin "153") (pinfunction "HDMI0_HOTPLUG_153") (pintype "passive"))
    )
    (net (code "58") (name "Net-(J3-SCL)") (class "Default")
      (node (ref "J3") (pin "15") (pinfunction "SCL_15") (pintype "passive"))
      (node (ref "RPI-CM2") (pin "200") (pinfunction "HDMI0_SCL_200") (pintype "passive"))
    )
    (net (code "59") (name "Net-(J3-SDA)") (class "Default")
      (node (ref "J3") (pin "16") (pinfunction "SDA_16") (pintype "passive"))
      (node (ref "RPI-CM2") (pin "199") (pinfunction "HDMI0_SDA_199") (pintype "passive"))
    )
    (net (code "60") (name "Net-(J3-TMDSCLOCK+)") (class "Default")
      (node (ref "J3") (pin "10") (pinfunction "TMDSCLOCK+_10") (pintype "passive"))
      (node (ref "RPI-CM2") (pin "188") (pinfunction "HDMI0_CLK_P_188") (pintype "passive"))
    )
    (net (code "61") (name "Net-(J3-TMDSCLOCK-)") (class "Default")
      (node (ref "J3") (pin "12") (pinfunction "TMDSCLOCK-_12") (pintype "passive"))
      (node (ref "RPI-CM2") (pin "190") (pinfunction "HDMI0_CLK_N_190") (pintype "passive"))
    )
    (net (code "62") (name "Net-(J3-TMDSDATA0+)") (class "Default")
      (node (ref "J3") (pin "7") (pinfunction "TMDSDATA0+_7") (pintype "passive"))
      (node (ref "RPI-CM2") (pin "182") (pinfunction "HDMI0_TX0_P_182") (pintype "passive"))
    )
    (net (code "63") (name "Net-(J3-TMDSDATA0-)") (class "Default")
      (node (ref "J3") (pin "9") (pinfunction "TMDSDATA0-_9") (pintype "passive"))
      (node (ref "RPI-CM2") (pin "184") (pinfunction "HDMI0_TX0_N_184") (pintype "passive"))
    )
    (net (code "64") (name "Net-(J3-TMDSDATA1+)") (class "Default")
      (node (ref "J3") (pin "4") (pinfunction "TMDSDATA1+_4") (pintype "passive"))
      (node (ref "RPI-CM2") (pin "176") (pinfunction "HDMI0_TX1_P_176") (pintype "passive"))
    )
    (net (code "65") (name "Net-(J3-TMDSDATA1-)") (class "Default")
      (node (ref "J3") (pin "6") (pinfunction "TMDSDATA1-_6") (pintype "passive"))
      (node (ref "RPI-CM2") (pin "178") (pinfunction "HDMI0_TX1_N_178") (pintype "passive"))
    )
    (net (code "66") (name "Net-(J3-TMDSDATA2+)") (class "Default")
      (node (ref "J3") (pin "1") (pinfunction "TMDSDATA2+_1") (pintype "passive"))
      (node (ref "RPI-CM2") (pin "170") (pinfunction "HDMI0_TX2_P_170") (pintype "passive"))
    )
    (net (code "67") (name "Net-(J3-TMDSDATA2-)") (class "Default")
      (node (ref "J3") (pin "3") (pinfunction "TMDSDATA2-_3") (pintype "passive"))
      (node (ref "RPI-CM2") (pin "172") (pinfunction "HDMI0_TX2_N_172") (pintype "passive"))
    )
    (net (code "68") (name "Net-(J4-D+)") (class "Default")
      (node (ref "J4") (pin "3") (pinfunction "D+_3") (pintype "bidirectional"))
      (node (ref "U1") (pin "7") (pinfunction "HSD1+_7") (pintype "power_in"))
    )
    (net (code "69") (name "Net-(J4-D-)") (class "Default")
      (node (ref "J4") (pin "2") (pinfunction "D-_2") (pintype "bidirectional"))
      (node (ref "U1") (pin "6") (pinfunction "HSD1-_6") (pintype "bidirectional"))
    )
    (net (code "70") (name "Net-(LED1-PadC)") (class "Default")
      (node (ref "LED1") (pin "C") (pinfunction "C_C") (pintype "passive"))
      (node (ref "R4") (pin "2") (pinfunction "2_2") (pintype "passive"))
    )
    (net (code "71") (name "Net-(LED2-PadC)") (class "Default")
      (node (ref "LED2") (pin "C") (pinfunction "C_C") (pintype "passive"))
      (node (ref "R5") (pin "2") (pinfunction "2_2") (pintype "passive"))
    )
    (net (code "72") (name "Net-(RPI-CM2A-GPIO_VREF)") (class "Default")
      (node (ref "IOREF") (pin "2") (pinfunction "2_2") (pintype "passive"))
      (node (ref "RPI-CM2") (pin "78") (pinfunction "GPIO_VREF_78") (pintype "passive"))
    )
    (net (code "73") (name "Net-(RPI-CM2B-USB_N)") (class "Default")
      (node (ref "RPI-CM2") (pin "103") (pinfunction "USB_N_103") (pintype "passive"))
      (node (ref "U1") (pin "4") (pinfunction "D-_4") (pintype "bidirectional"))
    )
    (net (code "74") (name "Net-(RPI-CM2B-USB_OTG_ID)") (class "Default")
      (node (ref "R6") (pin "2") (pinfunction "2_2") (pintype "passive"))
      (node (ref "RPI-CM2") (pin "101") (pinfunction "USB_OTG_ID_101") (pintype "passive"))
      (node (ref "U1") (pin "2") (pinfunction "SEL_2") (pintype "bidirectional"))
    )
    (net (code "75") (name "Net-(RPI-CM2B-USB_P)") (class "Default")
      (node (ref "RPI-CM2") (pin "105") (pinfunction "USB_P_105") (pintype "passive"))
      (node (ref "U1") (pin "3") (pinfunction "D+_3") (pintype "bidirectional"))
    )
    (net (code "76") (name "PWR_LED") (class "Default")
      (node (ref "IC2") (pin "2") (pinfunction "A_2") (pintype "bidirectional"))
      (node (ref "RPI-CM2") (pin "95") (pinfunction "PI_LED_~{PWR}_95") (pintype "passive"))
    )
    (net (code "77") (name "RPIBOOT") (class "Default")
      (node (ref "JP1") (pin "5") (pinfunction "5_5") (pintype "passive"))
      (node (ref "RPI-CM2") (pin "93") (pinfunction "~{RPIBOOT}_93") (pintype "passive"))
    )
    (net (code "78") (name "RUN_PG") (class "Default")
      (node (ref "IC3") (pin "2") (pinfunction "A_2") (pintype "bidirectional"))
      (node (ref "RPI-CM2") (pin "92") (pinfunction "RUN_PG_92") (pintype "passive"))
    )
    (net (code "79") (name "SD_CLK") (class "Default")
      (node (ref "J1") (pin "5") (pinfunction "CLK(SCK)_5") (pintype "bidirectional"))
      (node (ref "RPI-CM2") (pin "57") (pinfunction "SD_CLK_57") (pintype "passive"))
    )
    (net (code "80") (name "SD_CMD") (class "Default")
      (node (ref "J1") (pin "3") (pinfunction "CMD(DI)_3") (pintype "bidirectional"))
      (node (ref "RPI-CM2") (pin "62") (pinfunction "SD_CMD_62") (pintype "passive"))
    )
    (net (code "81") (name "SD_DAT0") (class "Default")
      (node (ref "J1") (pin "7") (pinfunction "DAT0(DO)_7") (pintype "bidirectional"))
      (node (ref "RPI-CM2") (pin "63") (pinfunction "SD_DAT0_63") (pintype "passive"))
    )
    (net (code "82") (name "SD_DAT1") (class "Default")
      (node (ref "J1") (pin "8") (pinfunction "DAT1(RSV)_8") (pintype "bidirectional"))
      (node (ref "RPI-CM2") (pin "67") (pinfunction "SD_DAT1_67") (pintype "passive"))
    )
    (net (code "83") (name "SD_DAT2") (class "Default")
      (node (ref "J1") (pin "1") (pinfunction "DAT2(NC)_1") (pintype "bidirectional"))
      (node (ref "RPI-CM2") (pin "69") (pinfunction "SD_DAT2_69") (pintype "passive"))
    )
    (net (code "84") (name "SD_DAT3") (class "Default")
      (node (ref "J1") (pin "2") (pinfunction "CD/DAT3(~{CS})_2") (pintype "bidirectional"))
      (node (ref "RPI-CM2") (pin "61") (pinfunction "SD_DAT3_61") (pintype "passive"))
    )
    (net (code "85") (name "SD_PWR") (class "Default")
      (node (ref "C1") (pin "1") (pinfunction "1_1") (pintype "passive"))
      (node (ref "IC1") (pin "1") (pinfunction "VOUT_1") (pintype "bidirectional"))
      (node (ref "J1") (pin "4") (pinfunction "VDD_4") (pintype "bidirectional"))
    )
    (net (code "86") (name "SD_PWR_ON") (class "Default")
      (node (ref "IC1") (pin "4") (pinfunction "EN/~{EN}_4") (pintype "bidirectional"))
      (node (ref "R1") (pin "2") (pinfunction "2_2") (pintype "passive"))
      (node (ref "RPI-CM2") (pin "75") (pinfunction "SD_PWR_ON_75") (pintype "passive"))
    )
    (net (code "87") (name "VBUS") (class "Default")
      (node (ref "C11") (pin "1") (pinfunction "1_1") (pintype "passive"))
      (node (ref "C12") (pin "1") (pinfunction "1_1") (pintype "passive"))
      (node (ref "C13") (pin "1") (pinfunction "1_1") (pintype "passive"))
      (node (ref "C14") (pin "1") (pinfunction "1_1") (pintype "passive"))
      (node (ref "C15") (pin "1") (pinfunction "+_1") (pintype "passive"))
      (node (ref "IC6") (pin "6") (pinfunction "OUT_6") (pintype "bidirectional"))
      (node (ref "J4") (pin "1") (pinfunction "VBUS_1") (pintype "bidirectional"))
    )
    (net (code "88") (name "VBUS_OTG") (class "Default")
      (node (ref "IC6") (pin "3") (pinfunction "EN/~{EN}_3") (pintype "bidirectional"))
      (node (ref "J7") (pin "1") (pinfunction "VBUS_1") (pintype "passive"))
      (node (ref "R6") (pin "1") (pinfunction "1_1") (pintype "passive"))
      (node (ref "R7") (pin "2") (pinfunction "2_2") (pintype "passive"))
    )
    (net (code "89") (name "unconnected-(IC1-~{FLG}-Pad3)") (class "Default")
      (node (ref "IC1") (pin "3") (pinfunction "~{FLG}_3") (pintype "bidirectional"))
    )
    (net (code "90") (name "unconnected-(IC4-D2+-Pad4)") (class "Default")
      (node (ref "IC4") (pin "4") (pinfunction "D2+_4") (pintype "bidirectional"))
    )
    (net (code "91") (name "unconnected-(IC4-D2--Pad5)") (class "Default")
      (node (ref "IC4") (pin "5") (pinfunction "D2-_5") (pintype "bidirectional"))
    )
    (net (code "92") (name "unconnected-(IC4-N.C._1-Pad6)") (class "Default")
      (node (ref "IC4") (pin "6") (pinfunction "N.C._1_6") (pintype "bidirectional"))
    )
    (net (code "93") (name "unconnected-(IC4-N.C._2-Pad7)") (class "Default")
      (node (ref "IC4") (pin "7") (pinfunction "N.C._2_7") (pintype "bidirectional"))
    )
    (net (code "94") (name "unconnected-(IC4-N.C._3-Pad9)") (class "Default")
      (node (ref "IC4") (pin "9") (pinfunction "N.C._3_9") (pintype "bidirectional"))
    )
    (net (code "95") (name "unconnected-(IC4-N.C._4-Pad10)") (class "Default")
      (node (ref "IC4") (pin "10") (pinfunction "N.C._4_10") (pintype "bidirectional"))
    )
    (net (code "96") (name "unconnected-(IC6-~{FAULT}-Pad4)") (class "Default")
      (node (ref "IC6") (pin "4") (pinfunction "~{FAULT}_4") (pintype "bidirectional"))
    )
    (net (code "97") (name "unconnected-(IC7-~{FAULT}-Pad4)") (class "Default")
      (node (ref "IC7") (pin "4") (pinfunction "~{FAULT}_4") (pintype "bidirectional"))
    )
    (net (code "98") (name "unconnected-(J2-Pad1)") (class "Default")
      (node (ref "J2") (pin "1") (pinfunction "1_1") (pintype "passive"))
    )
    (net (code "99") (name "unconnected-(J2-Pad2)") (class "Default")
      (node (ref "J2") (pin "2") (pinfunction "2_2") (pintype "passive"))
    )
    (net (code "100") (name "unconnected-(J2-Pad3)") (class "Default")
      (node (ref "J2") (pin "3") (pinfunction "3_3") (pintype "passive"))
    )
    (net (code "101") (name "unconnected-(J2-Pad4)") (class "Default")
      (node (ref "J2") (pin "4") (pinfunction "4_4") (pintype "passive"))
    )
    (net (code "102") (name "unconnected-(J2-Pad5)") (class "Default")
      (node (ref "J2") (pin "5") (pinfunction "5_5") (pintype "passive"))
    )
    (net (code "103") (name "unconnected-(J2-Pad6)") (class "Default")
      (node (ref "J2") (pin "6") (pinfunction "6_6") (pintype "passive"))
    )
    (net (code "104") (name "unconnected-(J2-Pad7)") (class "Default")
      (node (ref "J2") (pin "7") (pinfunction "7_7") (pintype "passive"))
    )
    (net (code "105") (name "unconnected-(J2-Pad8)") (class "Default")
      (node (ref "J2") (pin "8") (pinfunction "8_8") (pintype "passive"))
    )
    (net (code "106") (name "unconnected-(J3-UTILITY{slash}HEAC+-Pad14)") (class "Default")
      (node (ref "J3") (pin "14") (pinfunction "UTILITY/HEAC+_14") (pintype "passive"))
    )
    (net (code "107") (name "unconnected-(J7-ID-Pad4)") (class "Default")
      (node (ref "J7") (pin "4") (pinfunction "ID_4") (pintype "passive"))
    )
    (net (code "108") (name "unconnected-(RPI-CM2A-ANALOGP0-Pad96)") (class "Default")
      (node (ref "RPI-CM2") (pin "96") (pinfunction "ANALOGP0_96") (pintype "passive"))
    )
    (net (code "109") (name "unconnected-(RPI-CM2A-ANALOGP1-Pad94)") (class "Default")
      (node (ref "RPI-CM2") (pin "94") (pinfunction "ANALOGP1_94") (pintype "passive"))
    )
    (net (code "110") (name "unconnected-(RPI-CM2A-BT_~{DISABLE}-Pad91)") (class "Default")
      (node (ref "RPI-CM2") (pin "91") (pinfunction "BT_~{DISABLE}_91") (pintype "passive"))
    )
    (net (code "111") (name "unconnected-(RPI-CM2A-CAMERA_GPIO-Pad97)") (class "Default")
      (node (ref "RPI-CM2") (pin "97") (pinfunction "CAMERA_GPIO_97") (pintype "passive"))
    )
    (net (code "112") (name "unconnected-(RPI-CM2A-ETH_PAIR0_N-Pad10)") (class "Default")
      (node (ref "RPI-CM2") (pin "10") (pinfunction "ETH_PAIR0_N_10") (pintype "passive"))
    )
    (net (code "113") (name "unconnected-(RPI-CM2A-ETH_PAIR0_P-Pad12)") (class "Default")
      (node (ref "RPI-CM2") (pin "12") (pinfunction "ETH_PAIR0_P_12") (pintype "passive"))
    )
    (net (code "114") (name "unconnected-(RPI-CM2A-ETH_PAIR1_N-Pad6)") (class "Default")
      (node (ref "RPI-CM2") (pin "6") (pinfunction "ETH_PAIR1_N_6") (pintype "passive"))
    )
    (net (code "115") (name "unconnected-(RPI-CM2A-ETH_PAIR1_P-Pad4)") (class "Default")
      (node (ref "RPI-CM2") (pin "4") (pinfunction "ETH_PAIR1_P_4") (pintype "passive"))
    )
    (net (code "116") (name "unconnected-(RPI-CM2A-ETH_PAIR2_N-Pad9)") (class "Default")
      (node (ref "RPI-CM2") (pin "9") (pinfunction "ETH_PAIR2_N_9") (pintype "passive"))
    )
    (net (code "117") (name "unconnected-(RPI-CM2A-ETH_PAIR2_P-Pad11)") (class "Default")
      (node (ref "RPI-CM2") (pin "11") (pinfunction "ETH_PAIR2_P_11") (pintype "passive"))
    )
    (net (code "118") (name "unconnected-(RPI-CM2A-ETH_PAIR3_N-Pad5)") (class "Default")
      (node (ref "RPI-CM2") (pin "5") (pinfunction "ETH_PAIR3_N_5") (pintype "passive"))
    )
    (net (code "119") (name "unconnected-(RPI-CM2A-ETH_PAIR3_P-Pad3)") (class "Default")
      (node (ref "RPI-CM2") (pin "3") (pinfunction "ETH_PAIR3_P_3") (pintype "passive"))
    )
    (net (code "120") (name "unconnected-(RPI-CM2A-ETH_SYNC_IN-Pad16)") (class "Default")
      (node (ref "RPI-CM2") (pin "16") (pinfunction "ETH_SYNC_IN_16") (pintype "passive"))
    )
    (net (code "121") (name "unconnected-(RPI-CM2A-ETH_SYNC_OUT-Pad18)") (class "Default")
      (node (ref "RPI-CM2") (pin "18") (pinfunction "ETH_SYNC_OUT_18") (pintype "passive"))
    )
    (net (code "122") (name "unconnected-(RPI-CM2A-ETH_~{LED1}-Pad19)") (class "Default")
      (node (ref "RPI-CM2") (pin "19") (pinfunction "ETH_~{LED1}_19") (pintype "passive"))
    )
    (net (code "123") (name "unconnected-(RPI-CM2A-RESERVED-Pad76)") (class "Default")
      (node (ref "RPI-CM2") (pin "76") (pinfunction "RESERVED_76") (pintype "passive"))
    )
    (net (code "124") (name "unconnected-(RPI-CM2A-SCL0-Pad80)") (class "Default")
      (node (ref "RPI-CM2") (pin "80") (pinfunction "SCL0_80") (pintype "passive"))
    )
    (net (code "125") (name "unconnected-(RPI-CM2A-SDA0-Pad82)") (class "Default")
      (node (ref "RPI-CM2") (pin "82") (pinfunction "SDA0_82") (pintype "passive"))
    )
    (net (code "126") (name "unconnected-(RPI-CM2A-SD_DAT4-Pad68)") (class "Default")
      (node (ref "RPI-CM2") (pin "68") (pinfunction "SD_DAT4_68") (pintype "passive"))
    )
    (net (code "127") (name "unconnected-(RPI-CM2A-SD_DAT5-Pad64)") (class "Default")
      (node (ref "RPI-CM2") (pin "64") (pinfunction "SD_DAT5_64") (pintype "passive"))
    )
    (net (code "128") (name "unconnected-(RPI-CM2A-SD_DAT6-Pad72)") (class "Default")
      (node (ref "RPI-CM2") (pin "72") (pinfunction "SD_DAT6_72") (pintype "passive"))
    )
    (net (code "129") (name "unconnected-(RPI-CM2A-SD_DAT7-Pad70)") (class "Default")
      (node (ref "RPI-CM2") (pin "70") (pinfunction "SD_DAT7_70") (pintype "passive"))
    )
    (net (code "130") (name "unconnected-(RPI-CM2A-SD_VDD_OVERRIDE-Pad73)") (class "Default")
      (node (ref "RPI-CM2") (pin "73") (pinfunction "SD_VDD_OVERRIDE_73") (pintype "passive"))
    )
    (net (code "131") (name "unconnected-(RPI-CM2A-WL_~{DISABLE}-Pad89)") (class "Default")
      (node (ref "RPI-CM2") (pin "89") (pinfunction "WL_~{DISABLE}_89") (pintype "passive"))
    )
    (net (code "132") (name "unconnected-(RPI-CM2A-~{EXTRST}-Pad100)") (class "Default")
      (node (ref "RPI-CM2") (pin "100") (pinfunction "~{EXTRST}_100") (pintype "passive"))
    )
    (net (code "133") (name "unconnected-(RPI-CM2B-CAM0_C_N-Pad140)") (class "Default")
      (node (ref "RPI-CM2") (pin "140") (pinfunction "CAM0_C_N_140") (pintype "passive"))
    )
    (net (code "134") (name "unconnected-(RPI-CM2B-CAM0_C_P-Pad142)") (class "Default")
      (node (ref "RPI-CM2") (pin "142") (pinfunction "CAM0_C_P_142") (pintype "passive"))
    )
    (net (code "135") (name "unconnected-(RPI-CM2B-CAM0_D0_N-Pad128)") (class "Default")
      (node (ref "RPI-CM2") (pin "128") (pinfunction "CAM0_D0_N_128") (pintype "passive"))
    )
    (net (code "136") (name "unconnected-(RPI-CM2B-CAM0_D0_P-Pad130)") (class "Default")
      (node (ref "RPI-CM2") (pin "130") (pinfunction "CAM0_D0_P_130") (pintype "passive"))
    )
    (net (code "137") (name "unconnected-(RPI-CM2B-CAM0_D1_N-Pad134)") (class "Default")
      (node (ref "RPI-CM2") (pin "134") (pinfunction "CAM0_D1_N_134") (pintype "passive"))
    )
    (net (code "138") (name "unconnected-(RPI-CM2B-CAM0_D1_P-Pad136)") (class "Default")
      (node (ref "RPI-CM2") (pin "136") (pinfunction "CAM0_D1_P_136") (pintype "passive"))
    )
    (net (code "139") (name "unconnected-(RPI-CM2B-CAM1_C_N-Pad127)") (class "Default")
      (node (ref "RPI-CM2") (pin "127") (pinfunction "CAM1_C_N_127") (pintype "passive"))
    )
    (net (code "140") (name "unconnected-(RPI-CM2B-CAM1_C_P-Pad129)") (class "Default")
      (node (ref "RPI-CM2") (pin "129") (pinfunction "CAM1_C_P_129") (pintype "passive"))
    )
    (net (code "141") (name "unconnected-(RPI-CM2B-CAM1_D0_N-Pad115)") (class "Default")
      (node (ref "RPI-CM2") (pin "115") (pinfunction "CAM1_D0_N_115") (pintype "passive"))
    )
    (net (code "142") (name "unconnected-(RPI-CM2B-CAM1_D0_P-Pad117)") (class "Default")
      (node (ref "RPI-CM2") (pin "117") (pinfunction "CAM1_D0_P_117") (pintype "passive"))
    )
    (net (code "143") (name "unconnected-(RPI-CM2B-CAM1_D1_N-Pad121)") (class "Default")
      (node (ref "RPI-CM2") (pin "121") (pinfunction "CAM1_D1_N_121") (pintype "passive"))
    )
    (net (code "144") (name "unconnected-(RPI-CM2B-CAM1_D1_P-Pad123)") (class "Default")
      (node (ref "RPI-CM2") (pin "123") (pinfunction "CAM1_D1_P_123") (pintype "passive"))
    )
    (net (code "145") (name "unconnected-(RPI-CM2B-CAM1_D2_N-Pad133)") (class "Default")
      (node (ref "RPI-CM2") (pin "133") (pinfunction "CAM1_D2_N_133") (pintype "passive"))
    )
    (net (code "146") (name "unconnected-(RPI-CM2B-CAM1_D2_P-Pad135)") (class "Default")
      (node (ref "RPI-CM2") (pin "135") (pinfunction "CAM1_D2_P_135") (pintype "passive"))
    )
    (net (code "147") (name "unconnected-(RPI-CM2B-CAM1_D3_N-Pad139)") (class "Default")
      (node (ref "RPI-CM2") (pin "139") (pinfunction "CAM1_D3_N_139") (pintype "passive"))
    )
    (net (code "148") (name "unconnected-(RPI-CM2B-CAM1_D3_P-Pad141)") (class "Default")
      (node (ref "RPI-CM2") (pin "141") (pinfunction "CAM1_D3_P_141") (pintype "passive"))
    )
    (net (code "149") (name "unconnected-(RPI-CM2B-DSI0_C_N-Pad169)") (class "Default")
      (node (ref "RPI-CM2") (pin "169") (pinfunction "DSI0_C_N_169") (pintype "passive"))
    )
    (net (code "150") (name "unconnected-(RPI-CM2B-DSI0_C_P-Pad171)") (class "Default")
      (node (ref "RPI-CM2") (pin "171") (pinfunction "DSI0_C_P_171") (pintype "passive"))
    )
    (net (code "151") (name "unconnected-(RPI-CM2B-DSI0_D0_N-Pad157)") (class "Default")
      (node (ref "RPI-CM2") (pin "157") (pinfunction "DSI0_D0_N_157") (pintype "passive"))
    )
    (net (code "152") (name "unconnected-(RPI-CM2B-DSI0_D0_P-Pad159)") (class "Default")
      (node (ref "RPI-CM2") (pin "159") (pinfunction "DSI0_D0_P_159") (pintype "passive"))
    )
    (net (code "153") (name "unconnected-(RPI-CM2B-DSI0_D1_N-Pad163)") (class "Default")
      (node (ref "RPI-CM2") (pin "163") (pinfunction "DSI0_D1_N_163") (pintype "passive"))
    )
    (net (code "154") (name "unconnected-(RPI-CM2B-DSI0_D1_P-Pad165)") (class "Default")
      (node (ref "RPI-CM2") (pin "165") (pinfunction "DSI0_D1_P_165") (pintype "passive"))
    )
    (net (code "155") (name "unconnected-(RPI-CM2B-DSI1_C_N-Pad187)") (class "Default")
      (node (ref "RPI-CM2") (pin "187") (pinfunction "DSI1_C_N_187") (pintype "passive"))
    )
    (net (code "156") (name "unconnected-(RPI-CM2B-DSI1_C_P-Pad189)") (class "Default")
      (node (ref "RPI-CM2") (pin "189") (pinfunction "DSI1_C_P_189") (pintype "passive"))
    )
    (net (code "157") (name "unconnected-(RPI-CM2B-DSI1_D0_N-Pad175)") (class "Default")
      (node (ref "RPI-CM2") (pin "175") (pinfunction "DSI1_D0_N_175") (pintype "passive"))
    )
    (net (code "158") (name "unconnected-(RPI-CM2B-DSI1_D0_P-Pad177)") (class "Default")
      (node (ref "RPI-CM2") (pin "177") (pinfunction "DSI1_D0_P_177") (pintype "passive"))
    )
    (net (code "159") (name "unconnected-(RPI-CM2B-DSI1_D1_N-Pad181)") (class "Default")
      (node (ref "RPI-CM2") (pin "181") (pinfunction "DSI1_D1_N_181") (pintype "passive"))
    )
    (net (code "160") (name "unconnected-(RPI-CM2B-DSI1_D1_P-Pad183)") (class "Default")
      (node (ref "RPI-CM2") (pin "183") (pinfunction "DSI1_D1_P_183") (pintype "passive"))
    )
    (net (code "161") (name "unconnected-(RPI-CM2B-DSI1_D2_N-Pad193)") (class "Default")
      (node (ref "RPI-CM2") (pin "193") (pinfunction "DSI1_D2_N_193") (pintype "passive"))
    )
    (net (code "162") (name "unconnected-(RPI-CM2B-DSI1_D2_P-Pad195)") (class "Default")
      (node (ref "RPI-CM2") (pin "195") (pinfunction "DSI1_D2_P_195") (pintype "passive"))
    )
    (net (code "163") (name "unconnected-(RPI-CM2B-DSI1_D3_N-Pad194)") (class "Default")
      (node (ref "RPI-CM2") (pin "194") (pinfunction "DSI1_D3_N_194") (pintype "passive"))
    )
    (net (code "164") (name "unconnected-(RPI-CM2B-DSI1_D3_P-Pad196)") (class "Default")
      (node (ref "RPI-CM2") (pin "196") (pinfunction "DSI1_D3_P_196") (pintype "passive"))
    )
    (net (code "165") (name "unconnected-(RPI-CM2B-HDMI1_CEC-Pad149)") (class "Default")
      (node (ref "RPI-CM2") (pin "149") (pinfunction "HDMI1_CEC_149") (pintype "passive"))
    )
    (net (code "166") (name "unconnected-(RPI-CM2B-HDMI1_CLK_N-Pad166)") (class "Default")
      (node (ref "RPI-CM2") (pin "166") (pinfunction "HDMI1_CLK_N_166") (pintype "passive"))
    )
    (net (code "167") (name "unconnected-(RPI-CM2B-HDMI1_CLK_P-Pad164)") (class "Default")
      (node (ref "RPI-CM2") (pin "164") (pinfunction "HDMI1_CLK_P_164") (pintype "passive"))
    )
    (net (code "168") (name "unconnected-(RPI-CM2B-HDMI1_HOTPLUG-Pad143)") (class "Default")
      (node (ref "RPI-CM2") (pin "143") (pinfunction "HDMI1_HOTPLUG_143") (pintype "passive"))
    )
    (net (code "169") (name "unconnected-(RPI-CM2B-HDMI1_SCL-Pad147)") (class "Default")
      (node (ref "RPI-CM2") (pin "147") (pinfunction "HDMI1_SCL_147") (pintype "passive"))
    )
    (net (code "170") (name "unconnected-(RPI-CM2B-HDMI1_SDA-Pad145)") (class "Default")
      (node (ref "RPI-CM2") (pin "145") (pinfunction "HDMI1_SDA_145") (pintype "passive"))
    )
    (net (code "171") (name "unconnected-(RPI-CM2B-HDMI1_TX0_N-Pad160)") (class "Default")
      (node (ref "RPI-CM2") (pin "160") (pinfunction "HDMI1_TX0_N_160") (pintype "passive"))
    )
    (net (code "172") (name "unconnected-(RPI-CM2B-HDMI1_TX0_P-Pad158)") (class "Default")
      (node (ref "RPI-CM2") (pin "158") (pinfunction "HDMI1_TX0_P_158") (pintype "passive"))
    )
    (net (code "173") (name "unconnected-(RPI-CM2B-HDMI1_TX1_N-Pad154)") (class "Default")
      (node (ref "RPI-CM2") (pin "154") (pinfunction "HDMI1_TX1_N_154") (pintype "passive"))
    )
    (net (code "174") (name "unconnected-(RPI-CM2B-HDMI1_TX1_P-Pad152)") (class "Default")
      (node (ref "RPI-CM2") (pin "152") (pinfunction "HDMI1_TX1_P_152") (pintype "passive"))
    )
    (net (code "175") (name "unconnected-(RPI-CM2B-HDMI1_TX2_N-Pad148)") (class "Default")
      (node (ref "RPI-CM2") (pin "148") (pinfunction "HDMI1_TX2_N_148") (pintype "passive"))
    )
    (net (code "176") (name "unconnected-(RPI-CM2B-HDMI1_TX2_P-Pad146)") (class "Default")
      (node (ref "RPI-CM2") (pin "146") (pinfunction "HDMI1_TX2_P_146") (pintype "passive"))
    )
    (net (code "177") (name "unconnected-(RPI-CM2B-PCIE_CLK_N-Pad112)") (class "Default")
      (node (ref "RPI-CM2") (pin "112") (pinfunction "PCIE_CLK_N_112") (pintype "passive"))
    )
    (net (code "178") (name "unconnected-(RPI-CM2B-PCIE_CLK_P-Pad110)") (class "Default")
      (node (ref "RPI-CM2") (pin "110") (pinfunction "PCIE_CLK_P_110") (pintype "passive"))
    )
    (net (code "179") (name "unconnected-(RPI-CM2B-PCIE_CLK_~{REQ}-Pad102)") (class "Default")
      (node (ref "RPI-CM2") (pin "102") (pinfunction "PCIE_CLK_~{REQ}_102") (pintype "passive"))
    )
    (net (code "180") (name "unconnected-(RPI-CM2B-PCIE_RX_N-Pad118)") (class "Default")
      (node (ref "RPI-CM2") (pin "118") (pinfunction "PCIE_RX_N_118") (pintype "passive"))
    )
    (net (code "181") (name "unconnected-(RPI-CM2B-PCIE_RX_P-Pad116)") (class "Default")
      (node (ref "RPI-CM2") (pin "116") (pinfunction "PCIE_RX_P_116") (pintype "passive"))
    )
    (net (code "182") (name "unconnected-(RPI-CM2B-PCIE_TX_N-Pad124)") (class "Default")
      (node (ref "RPI-CM2") (pin "124") (pinfunction "PCIE_TX_N_124") (pintype "passive"))
    )
    (net (code "183") (name "unconnected-(RPI-CM2B-PCIE_TX_P-Pad122)") (class "Default")
      (node (ref "RPI-CM2") (pin "122") (pinfunction "PCIE_TX_P_122") (pintype "passive"))
    )
    (net (code "184") (name "unconnected-(RPI-CM2B-PCIE_~{RST}-Pad109)") (class "Default")
      (node (ref "RPI-CM2") (pin "109") (pinfunction "PCIE_~{RST}_109") (pintype "passive"))
    )
    (net (code "185") (name "unconnected-(RPI-CM2B-RESERVED-Pad104)") (class "Default")
      (node (ref "RPI-CM2") (pin "104") (pinfunction "RESERVED_104") (pintype "passive"))
    )
    (net (code "186") (name "unconnected-(RPI-CM2B-RESERVED-Pad106)") (class "Default")
      (node (ref "RPI-CM2") (pin "106") (pinfunction "RESERVED_106") (pintype "passive"))
    )
    (net (code "187") (name "unconnected-(RPI-CM2B-VDAC_COMP-Pad111)") (class "Default")
      (node (ref "RPI-CM2") (pin "111") (pinfunction "VDAC_COMP_111") (pintype "passive"))
    )
  )
)
